# main.net
KiCad netlist of a schematic drawn in Altium Designer
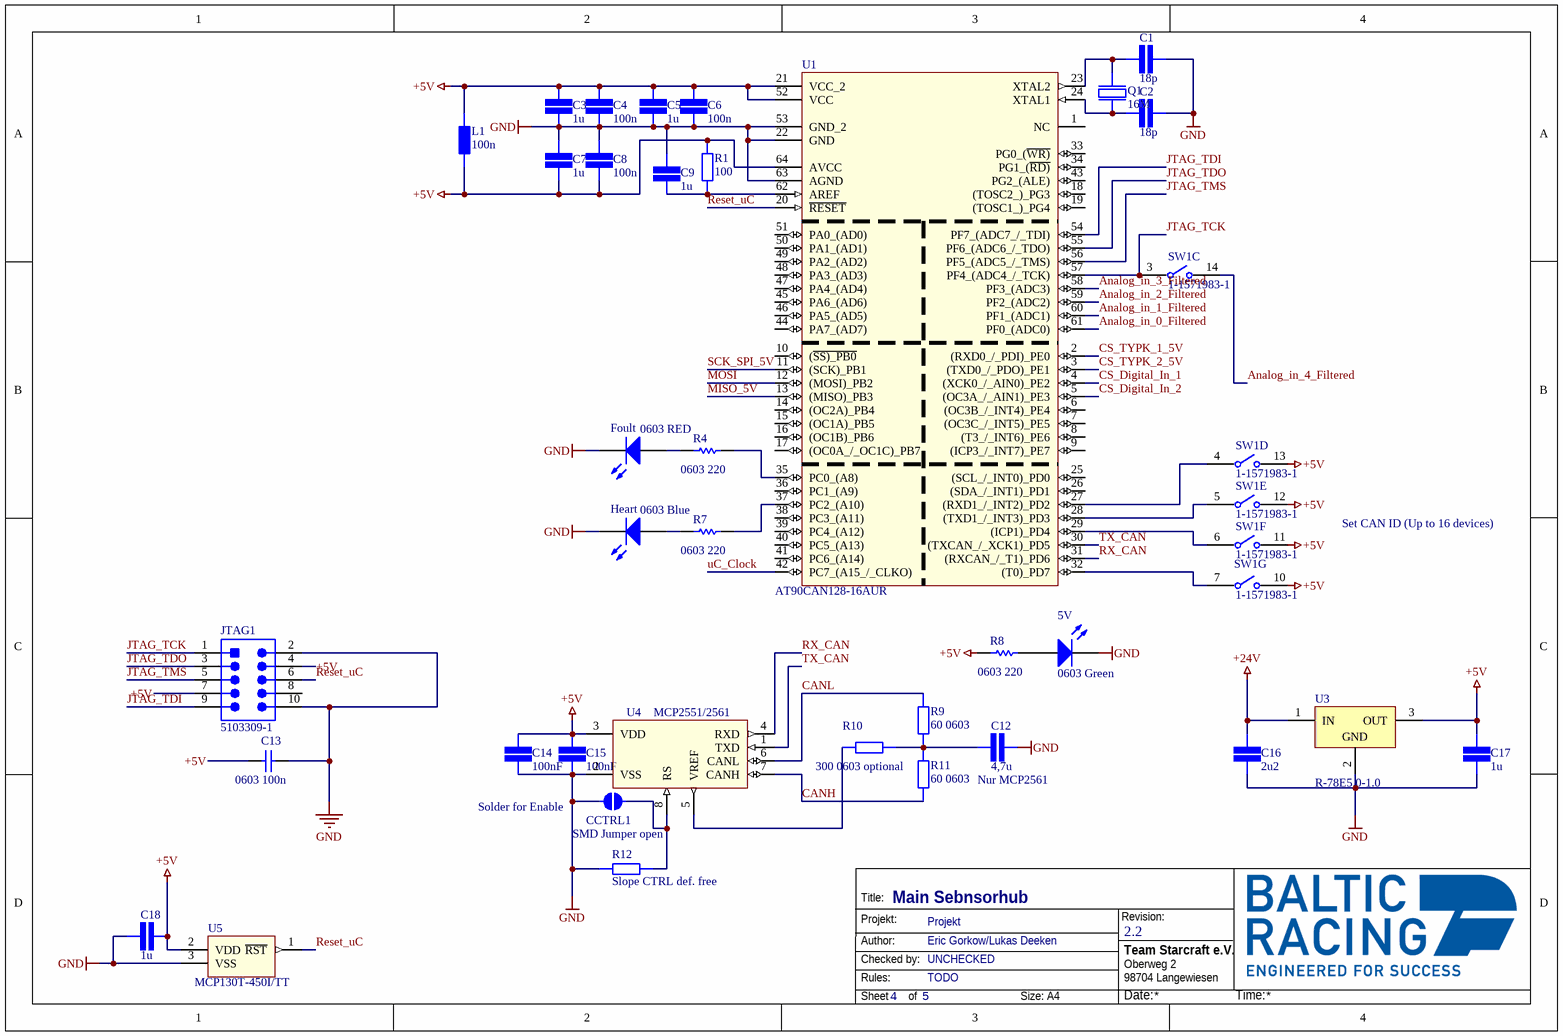
[diagram p0: main.SchDoc]

(export (version "E")
  (design (tool "Eeschema 10.0.6"))
  (components
    (comp (ref "5V")
      (value "0603 Green")
      (footprint "0603_A")
      (description "SMD mono-color Chip LED, WL-SMCW, Green")
      (fields (field (name "PARTNUMBER") "150060GS75000") (field (name "MANUFACTURER") "Wuerth Elektronik"))
      (libsource (lib "Altium Content Vault") (part "WE-LED_K1A2-2"))
    )
    (comp (ref "C1")
      (value "18p")
      (footprint "CAP 0603/1608")
      (description "Capacitor with multiple Footprints")
      (fields (field (name "Comment") "SMD Capacitor"))
      (libsource (lib "Standardbauteile") (part "SMD Capacitor"))
    )
    (comp (ref "C2")
      (value "18p")
      (footprint "CAP 0603/1608")
      (description "Capacitor with multiple Footprints")
      (fields (field (name "Comment") "SMD Capacitor"))
      (libsource (lib "Standardbauteile") (part "SMD Capacitor"))
    )
    (comp (ref "C3")
      (value "1u")
      (footprint "CAP 0603/1608")
      (description "Capacitor with multiple Footprints")
      (fields (field (name "Comment") "SMD Capacitor"))
      (libsource (lib "") (part "SMD Capacitor_1"))
    )
    (comp (ref "C4")
      (value "100n")
      (footprint "CAP 0603/1608")
      (description "Capacitor with multiple Footprints")
      (fields (field (name "Comment") "SMD Capacitor"))
      (libsource (lib "") (part "SMD Capacitor_1"))
    )
    (comp (ref "C5")
      (value "1u")
      (footprint "CAP 0603/1608")
      (description "Capacitor with multiple Footprints")
      (fields (field (name "Comment") "SMD Capacitor"))
      (libsource (lib "") (part "SMD Capacitor_1"))
    )
    (comp (ref "C6")
      (value "100n")
      (footprint "CAP 0603/1608")
      (description "Capacitor with multiple Footprints")
      (fields (field (name "Comment") "SMD Capacitor"))
      (libsource (lib "") (part "SMD Capacitor_1"))
    )
    (comp (ref "C7")
      (value "1u")
      (footprint "CAP 0603/1608")
      (description "Capacitor with multiple Footprints")
      (fields (field (name "Comment") "SMD Capacitor"))
      (libsource (lib "") (part "SMD Capacitor_1"))
    )
    (comp (ref "C8")
      (value "100n")
      (footprint "CAP 0603/1608")
      (description "Capacitor with multiple Footprints")
      (fields (field (name "Comment") "SMD Capacitor"))
      (libsource (lib "") (part "SMD Capacitor_1"))
    )
    (comp (ref "C9")
      (value "1u")
      (footprint "CAP 0603/1608")
      (description "Capacitor with multiple Footprints")
      (fields (field (name "Comment") "SMD Capacitor"))
      (libsource (lib "") (part "SMD Capacitor_1"))
    )
    (comp (ref "C12")
      (value "4,7u")
      (footprint "CAP 0603/1608")
      (description "Capacitor with multiple Footprints")
      (fields (field (name "Comment") "SMD Capacitor"))
      (libsource (lib "") (part "SMD Capacitor_2"))
    )
    (comp (ref "C13")
      (value "0603 100n")
      (footprint "CAPC0603(1608)100_L")
      (description "CAP 100nF 10V ±5% 0603 (1608 Metric) Thickness 1mm SMD")
      (fields (field (name "TOLERANCE") "Â±5%"))
      (libsource (lib "Altium Content Vault") (part "CAP"))
    )
    (comp (ref "C14")
      (value "100nF")
      (footprint "CAP 0603/1608")
      (description "Capacitor with multiple Footprints")
      (fields (field (name "Comment") "SMD Capacitor"))
      (libsource (lib "") (part "SMD Capacitor_1"))
    )
    (comp (ref "C15")
      (value "100nF")
      (footprint "CAP 0603/1608")
      (description "Capacitor with multiple Footprints")
      (fields (field (name "Comment") "SMD Capacitor"))
      (libsource (lib "") (part "SMD Capacitor_1"))
    )
    (comp (ref "C16")
      (value "2u2")
      (footprint "CAP 0603/1608")
      (description "Capacitor with multiple Footprints")
      (fields (field (name "Comment") "SMD Capacitor"))
      (libsource (lib "") (part "SMD Capacitor_1"))
    )
    (comp (ref "C17")
      (value "1u")
      (footprint "CAP 0603/1608")
      (description "Capacitor with multiple Footprints")
      (fields (field (name "Comment") "SMD Capacitor"))
      (libsource (lib "") (part "SMD Capacitor_1"))
    )
    (comp (ref "C18")
      (value "1u")
      (footprint "CAP 0603/1608")
      (description "Capacitor with multiple Footprints")
      (fields (field (name "Comment") "SMD Capacitor"))
      (libsource (lib "Standardbauteile") (part "SMD Capacitor"))
    )
    (comp (ref "CCTRL1")
      (value "SMD Jumper open")
      (footprint "SMD-JUMPER-OPEN")
      (libsource (lib "Standardbauteile") (part "SMD Jumper open"))
    )
    (comp (ref "Foult")
      (value "0603 RED")
      (footprint "0603_A")
      (description "SMD mono-color Chip LED, WL-SMCW, Blue")
      (fields (field (name "PARTNUMBER") "150060BS75000") (field (name "MANUFACTURER") "Wuerth Elektronik"))
      (libsource (lib "Altium Content Vault") (part "WE-LED_K1A2-2"))
    )
    (comp (ref "Heart")
      (value "0603 Blue")
      (footprint "0603_A")
      (description "SMD mono-color Chip LED, WL-SMCW, Blue")
      (fields (field (name "PARTNUMBER") "150060BS75000") (field (name "MANUFACTURER") "Wuerth Elektronik"))
      (libsource (lib "Altium Content Vault") (part "WE-LED_K1A2-2"))
    )
    (comp (ref "JTAG1")
      (value "5103309-1")
      (footprint "TECO-5103309-1_V")
      (fields (field (name "MANUFACTURER") "TE Connectivity"))
      (libsource (lib "Altium Content Vault") (part "CN-2P-M-R10"))
    )
    (comp (ref "L1")
      (value "100n")
      (footprint "SMD-Inductor 1206")
      (fields (field (name "Comment") "SMD Inductor"))
      (libsource (lib "Standardbauteile") (part "SMD Inductor"))
    )
    (comp (ref "Q1")
      (value "16M")
      (footprint "NDK NX5032GA")
      (description "16 MHz Quartz")
      (libsource (lib "Standardbauteile") (part "16 MHz Quartz"))
    )
    (comp (ref "R1")
      (value "100")
      (footprint "STACKPOLE CSR0603")
      (description "Resistor with multiple footprints")
      (fields (field (name "Comment") "SMD Resistor"))
      (libsource (lib "Standardbauteile") (part "SMD Resistor"))
    )
    (comp (ref "R4")
      (value "0603 220")
      (footprint "RESC1609X50X30NL10T20")
      (fields (field (name "MANUFACTURER") "Vishay Dale") (field (name "PART NUMBER") "CRCW0603130KFKEA"))
      (libsource (lib "Altium Content Vault") (part "RES"))
    )
    (comp (ref "R7")
      (value "0603 220")
      (footprint "RESC1609X50X30NL10T20")
      (fields (field (name "MANUFACTURER") "Vishay Dale") (field (name "PART NUMBER") "CRCW0603130KFKEA"))
      (libsource (lib "Altium Content Vault") (part "RES"))
    )
    (comp (ref "R8")
      (value "0603 220")
      (footprint "RESC1608X55X25ML10T15")
      (description "Chip Resistor, 100 Ohm, +/- 1%, 0.1 W, -55 to 155 degC, 0603 (1608 Metric), RoHS, Tape and Reel")
      (fields (field (name "TOLERANCE") "1%") (field (name "MANUFACTURER") "Yageo"))
      (libsource (lib "Altium Content Vault") (part "RES-2"))
    )
    (comp (ref "R9")
      (value "60 0603")
      (footprint "STACKPOLE CSR0603")
      (description "Resistor with multiple footprints")
      (fields (field (name "Comment") "SMD Resistor"))
      (libsource (lib "Standardbauteile") (part "SMD Resistor"))
    )
    (comp (ref "R10")
      (value "300 0603 optional")
      (footprint "STACKPOLE CSR0603")
      (description "Resistor with multiple footprints")
      (fields (field (name "Comment") "SMD Resistor"))
      (libsource (lib "Standardbauteile") (part "SMD Resistor"))
    )
    (comp (ref "R11")
      (value "60 0603")
      (footprint "STACKPOLE CSR0603")
      (description "Resistor with multiple footprints")
      (fields (field (name "Comment") "SMD Resistor"))
      (libsource (lib "Standardbauteile") (part "SMD Resistor"))
    )
    (comp (ref "R12")
      (value "Slope CTRL def. free")
      (footprint "STACKPOLE CSR0603")
      (description "Resistor with multiple footprints")
      (fields (field (name "Comment") "SMD Resistor"))
      (libsource (lib "Standardbauteile") (part "SMD Resistor"))
    )
    (comp (ref "SW1")
      (value "1-1571983-1")
      (footprint "FP-1-1571983-1-MFG")
      (description "SWITCH SLIDE DIP SPST 25MA 24V")
      (fields
        (field (name "MANUFACTURER") "TE Connectivity")
        (field (name "OCTOPART") "https://octopart.com/1-1571983-1-te+connectivity-40115518")
      )
      (libsource (lib "Altium Content Vault") (part "970e54b12a704161c1b4a03f85903bf"))
    )
    (comp (ref "U1")
      (value "AT90CAN128-16AUR")
      (footprint "*QFP80P1600X1600X120-64N")
      (description "Ic Mcu 8bit 128kb Flash 64tqfp")
      (fields (field (name "MP") "AT90CAN128-16AI") (field (name "MF") "Microchip"))
      (libsource (lib "Eric") (part "AT90CAN128-16AI"))
    )
    (comp (ref "U3")
      (value "R-78E5.0-1.0")
      (footprint "SIP3_RECOM")
      (description "Nonisolated 5V Switchmode converter")
      (libsource (lib "Standardbauteile") (part "R-78E05-1.0"))
    )
    (comp (ref "U4")
      (value "MCP2551/2561")
      (footprint "*SOIC127P600X175-8N")
      (description "MCP2551 Series 5.5 V 1 Mb/s Surface Mount High-Speed CAN Transceiver - SOIC-8")
      (fields (field (name "MP") "MCP2551-I/SN") (field (name "MF") "Microchip"))
      (libsource (lib "Eric") (part "MCP2551-I/SN"))
    )
    (comp (ref "U5")
      (value "MCP130T-450I/TT")
      (footprint "*SOT95P237X112-3N")
      (description "System Supervisors - Power Supply Monitors with Reset Generators Open Drain Low")
      (fields (field (name "MF") "Microchip") (field (name "MP") "MCP120T-450I/TT"))
      (libsource (lib "Eric") (part "MCP130T-450I/TT"))
    )
  )
  (nets
    (net (code "1") (name "+5V") (class "Default")
      (node (ref "C13") (pin "1") (pinfunction "1_1") (pintype "passive"))
      (node (ref "C14") (pin "2") (pinfunction "2_2") (pintype "passive"))
      (node (ref "C15") (pin "2") (pinfunction "2_2") (pintype "passive"))
      (node (ref "C17") (pin "2") (pinfunction "2_2") (pintype "passive"))
      (node (ref "C18") (pin "1") (pinfunction "1_1") (pintype "passive"))
      (node (ref "C3") (pin "2") (pinfunction "2_2") (pintype "passive"))
      (node (ref "C4") (pin "2") (pinfunction "2_2") (pintype "passive"))
      (node (ref "C5") (pin "2") (pinfunction "2_2") (pintype "passive"))
      (node (ref "C6") (pin "2") (pinfunction "2_2") (pintype "passive"))
      (node (ref "C7") (pin "1") (pinfunction "1_1") (pintype "passive"))
      (node (ref "C8") (pin "1") (pinfunction "1_1") (pintype "passive"))
      (node (ref "JTAG1") (pin "4") (pinfunction "4_4") (pintype "passive"))
      (node (ref "JTAG1") (pin "7") (pinfunction "7_7") (pintype "passive"))
      (node (ref "L1") (pin "1") (pinfunction "1_1") (pintype "passive"))
      (node (ref "L1") (pin "2") (pinfunction "2_2") (pintype "passive"))
      (node (ref "R1") (pin "2") (pinfunction "2_2") (pintype "passive"))
      (node (ref "R8") (pin "1") (pinfunction "1_1") (pintype "passive"))
      (node (ref "SW1") (pin "10") (pinfunction "10_10") (pintype "passive"))
      (node (ref "SW1") (pin "11") (pinfunction "11_11") (pintype "passive"))
      (node (ref "SW1") (pin "12") (pinfunction "12_12") (pintype "passive"))
      (node (ref "SW1") (pin "13") (pinfunction "13_13") (pintype "passive"))
      (node (ref "U1") (pin "21") (pinfunction "VCC_2_21") (pintype "power_in"))
      (node (ref "U1") (pin "52") (pinfunction "VCC_52") (pintype "power_in"))
      (node (ref "U1") (pin "64") (pinfunction "AVCC_64") (pintype "power_in"))
      (node (ref "U3") (pin "3") (pinfunction "OUT_3") (pintype "power_in"))
      (node (ref "U4") (pin "3") (pinfunction "VDD_3") (pintype "power_in"))
      (node (ref "U5") (pin "2") (pinfunction "VDD_2") (pintype "power_in"))
    )
    (net (code "2") (name "+24V") (class "Default")
      (node (ref "C16") (pin "2") (pinfunction "2_2") (pintype "passive"))
      (node (ref "U3") (pin "1") (pinfunction "IN_1") (pintype "power_in"))
    )
    (net (code "3") (name "/Analog_in_0_Filtered") (class "Default")
      (node (ref "U1") (pin "61") (pinfunction "PF0_(ADC0)_61") (pintype "bidirectional"))
    )
    (net (code "4") (name "/Analog_in_1_Filtered") (class "Default")
      (node (ref "U1") (pin "60") (pinfunction "PF1_(ADC1)_60") (pintype "bidirectional"))
    )
    (net (code "5") (name "/Analog_in_2_Filtered") (class "Default")
      (node (ref "U1") (pin "59") (pinfunction "PF2_(ADC2)_59") (pintype "bidirectional"))
    )
    (net (code "6") (name "/Analog_in_3_Filtered") (class "Default")
      (node (ref "U1") (pin "58") (pinfunction "PF3_(ADC3)_58") (pintype "bidirectional"))
    )
    (net (code "7") (name "/Analog_in_4_Filtered") (class "Default")
      (node (ref "SW1") (pin "14") (pinfunction "14_14") (pintype "passive"))
    )
    (net (code "8") (name "/CANH") (class "Default")
      (node (ref "R11") (pin "2") (pinfunction "2_2") (pintype "passive"))
      (node (ref "U4") (pin "7") (pinfunction "CANH_7") (pintype "bidirectional"))
    )
    (net (code "9") (name "/CANL") (class "Default")
      (node (ref "R9") (pin "1") (pinfunction "1_1") (pintype "passive"))
      (node (ref "U4") (pin "6") (pinfunction "CANL_6") (pintype "bidirectional"))
    )
    (net (code "10") (name "/CS_Digital_In_1") (class "Default")
      (node (ref "U1") (pin "4") (pinfunction "(XCK0_/_AIN0)_PE2_4") (pintype "bidirectional"))
    )
    (net (code "11") (name "/CS_Digital_In_2") (class "Default")
      (node (ref "U1") (pin "5") (pinfunction "(OC3A_/_AIN1)_PE3_5") (pintype "bidirectional"))
    )
    (net (code "12") (name "/CS_TYPK_1_5V") (class "Default")
      (node (ref "U1") (pin "2") (pinfunction "(RXD0_/_PDI)_PE0_2") (pintype "bidirectional"))
    )
    (net (code "13") (name "/CS_TYPK_2_5V") (class "Default")
      (node (ref "U1") (pin "3") (pinfunction "(TXD0_/_PDO)_PE1_3") (pintype "bidirectional"))
    )
    (net (code "14") (name "/JTAG_TCK") (class "Default")
      (node (ref "JTAG1") (pin "1") (pinfunction "1_1") (pintype "passive"))
      (node (ref "SW1") (pin "3") (pinfunction "3_3") (pintype "passive"))
      (node (ref "U1") (pin "57") (pinfunction "PF4_(ADC4_/_TCK)_57") (pintype "bidirectional"))
    )
    (net (code "15") (name "/JTAG_TDI") (class "Default")
      (node (ref "JTAG1") (pin "9") (pinfunction "9_9") (pintype "passive"))
      (node (ref "U1") (pin "54") (pinfunction "PF7_(ADC7_/_TDI)_54") (pintype "bidirectional"))
    )
    (net (code "16") (name "/JTAG_TDO") (class "Default")
      (node (ref "JTAG1") (pin "3") (pinfunction "3_3") (pintype "passive"))
      (node (ref "U1") (pin "55") (pinfunction "PF6_(ADC6_/_TDO)_55") (pintype "bidirectional"))
    )
    (net (code "17") (name "/JTAG_TMS") (class "Default")
      (node (ref "JTAG1") (pin "5") (pinfunction "5_5") (pintype "passive"))
      (node (ref "U1") (pin "56") (pinfunction "PF5_(ADC5_/_TMS)_56") (pintype "bidirectional"))
    )
    (net (code "18") (name "/MISO_5V") (class "Default")
      (node (ref "U1") (pin "13") (pinfunction "(MISO)_PB3_13") (pintype "bidirectional"))
    )
    (net (code "19") (name "/MOSI") (class "Default")
      (node (ref "U1") (pin "12") (pinfunction "(MOSI)_PB2_12") (pintype "bidirectional"))
    )
    (net (code "20") (name "/RX_CAN") (class "Default")
      (node (ref "U1") (pin "31") (pinfunction "(RXCAN_/_T1)_PD6_31") (pintype "bidirectional"))
      (node (ref "U4") (pin "4") (pinfunction "RXD_4") (pintype "output"))
    )
    (net (code "21") (name "/Reset_uC") (class "Default")
      (node (ref "JTAG1") (pin "6") (pinfunction "6_6") (pintype "passive"))
      (node (ref "U1") (pin "20") (pinfunction "~{RESET}_20") (pintype "input"))
      (node (ref "U5") (pin "1") (pinfunction "~{RST}_1") (pintype "output"))
    )
    (net (code "22") (name "/SCK_SPI_5V") (class "Default")
      (node (ref "U1") (pin "11") (pinfunction "(SCK)_PB1_11") (pintype "bidirectional"))
    )
    (net (code "23") (name "/TX_CAN") (class "Default")
      (node (ref "U1") (pin "30") (pinfunction "(TXCAN_/_XCK1)_PD5_30") (pintype "bidirectional"))
      (node (ref "U4") (pin "1") (pinfunction "TXD_1") (pintype "input"))
    )
    (net (code "24") (name "/uC_Clock") (class "Default")
      (node (ref "U1") (pin "42") (pinfunction "PC7_(A15_/_CLKO)_42") (pintype "bidirectional"))
    )
    (net (code "25") (name "GND") (class "Default")
      (node (ref "5V") (pin "1") (pinfunction "K_1") (pintype "passive"))
      (node (ref "C1") (pin "1") (pinfunction "1_1") (pintype "passive"))
      (node (ref "C12") (pin "2") (pinfunction "2_2") (pintype "passive"))
      (node (ref "C13") (pin "2") (pinfunction "2_2") (pintype "passive"))
      (node (ref "C14") (pin "1") (pinfunction "1_1") (pintype "passive"))
      (node (ref "C15") (pin "1") (pinfunction "1_1") (pintype "passive"))
      (node (ref "C16") (pin "1") (pinfunction "1_1") (pintype "passive"))
      (node (ref "C17") (pin "1") (pinfunction "1_1") (pintype "passive"))
      (node (ref "C18") (pin "2") (pinfunction "2_2") (pintype "passive"))
      (node (ref "C2") (pin "1") (pinfunction "1_1") (pintype "passive"))
      (node (ref "C3") (pin "1") (pinfunction "1_1") (pintype "passive"))
      (node (ref "C4") (pin "1") (pinfunction "1_1") (pintype "passive"))
      (node (ref "C5") (pin "1") (pinfunction "1_1") (pintype "passive"))
      (node (ref "C6") (pin "1") (pinfunction "1_1") (pintype "passive"))
      (node (ref "C7") (pin "2") (pinfunction "2_2") (pintype "passive"))
      (node (ref "C8") (pin "2") (pinfunction "2_2") (pintype "passive"))
      (node (ref "C9") (pin "2") (pinfunction "2_2") (pintype "passive"))
      (node (ref "CCTRL1") (pin "1") (pinfunction "1_1") (pintype "passive"))
      (node (ref "Foult") (pin "1") (pinfunction "K_1") (pintype "passive"))
      (node (ref "Heart") (pin "1") (pinfunction "K_1") (pintype "passive"))
      (node (ref "JTAG1") (pin "10") (pinfunction "10_10") (pintype "passive"))
      (node (ref "JTAG1") (pin "2") (pinfunction "2_2") (pintype "passive"))
      (node (ref "R12") (pin "1") (pinfunction "1_1") (pintype "passive"))
      (node (ref "U1") (pin "22") (pinfunction "GND_22") (pintype "passive"))
      (node (ref "U1") (pin "53") (pinfunction "GND_2_53") (pintype "passive"))
      (node (ref "U1") (pin "63") (pinfunction "AGND_63") (pintype "passive"))
      (node (ref "U3") (pin "2") (pinfunction "GND_2") (pintype "power_in"))
      (node (ref "U4") (pin "2") (pinfunction "VSS_2") (pintype "passive"))
      (node (ref "U5") (pin "3") (pinfunction "VSS_3") (pintype "power_in"))
    )
    (net (code "26") (name "Net-(5V-A)") (class "Default")
      (node (ref "5V") (pin "2") (pinfunction "A_2") (pintype "passive"))
      (node (ref "R8") (pin "2") (pinfunction "2_2") (pintype "passive"))
    )
    (net (code "27") (name "Net-(C12-Pad1)") (class "Default")
      (node (ref "C12") (pin "1") (pinfunction "1_1") (pintype "passive"))
      (node (ref "R10") (pin "2") (pinfunction "2_2") (pintype "passive"))
      (node (ref "R11") (pin "1") (pinfunction "1_1") (pintype "passive"))
      (node (ref "R9") (pin "2") (pinfunction "2_2") (pintype "passive"))
    )
    (net (code "28") (name "Net-(Foult-A)") (class "Default")
      (node (ref "Foult") (pin "2") (pinfunction "A_2") (pintype "passive"))
      (node (ref "R4") (pin "2") (pinfunction "2_2") (pintype "passive"))
    )
    (net (code "29") (name "Net-(Heart-A)") (class "Default")
      (node (ref "Heart") (pin "2") (pinfunction "A_2") (pintype "passive"))
      (node (ref "R7") (pin "2") (pinfunction "2_2") (pintype "passive"))
    )
    (net (code "30") (name "Net-(U1-(ICP1)_PD4)") (class "Default")
      (node (ref "SW1") (pin "6") (pinfunction "6_6") (pintype "passive"))
      (node (ref "U1") (pin "29") (pinfunction "(ICP1)_PD4_29") (pintype "bidirectional"))
    )
    (net (code "31") (name "Net-(U1-(RXD1_{slash}_INT2)_PD2)") (class "Default")
      (node (ref "SW1") (pin "4") (pinfunction "4_4") (pintype "passive"))
      (node (ref "U1") (pin "27") (pinfunction "(RXD1_/_INT2)_PD2_27") (pintype "bidirectional"))
    )
    (net (code "32") (name "Net-(U1-(T0)_PD7)") (class "Default")
      (node (ref "SW1") (pin "7") (pinfunction "7_7") (pintype "passive"))
      (node (ref "U1") (pin "32") (pinfunction "(T0)_PD7_32") (pintype "bidirectional"))
    )
    (net (code "33") (name "Net-(U1-(TXD1_{slash}_INT3)_PD3)") (class "Default")
      (node (ref "SW1") (pin "5") (pinfunction "5_5") (pintype "passive"))
      (node (ref "U1") (pin "28") (pinfunction "(TXD1_/_INT3)_PD3_28") (pintype "bidirectional"))
    )
    (net (code "34") (name "Net-(U1-AREF)") (class "Default")
      (node (ref "C9") (pin "1") (pinfunction "1_1") (pintype "passive"))
      (node (ref "R1") (pin "1") (pinfunction "1_1") (pintype "passive"))
      (node (ref "U1") (pin "62") (pinfunction "AREF_62") (pintype "input"))
    )
    (net (code "35") (name "Net-(U1-PC0_(A8))") (class "Default")
      (node (ref "R4") (pin "1") (pinfunction "1_1") (pintype "passive"))
      (node (ref "U1") (pin "35") (pinfunction "PC0_(A8)_35") (pintype "bidirectional"))
    )
    (net (code "36") (name "Net-(U1-PC2_(A10))") (class "Default")
      (node (ref "R7") (pin "1") (pinfunction "1_1") (pintype "passive"))
      (node (ref "U1") (pin "37") (pinfunction "PC2_(A10)_37") (pintype "bidirectional"))
    )
    (net (code "37") (name "Net-(U1-XTAL1)") (class "Default")
      (node (ref "C2") (pin "2") (pinfunction "2_2") (pintype "passive"))
      (node (ref "Q1") (pin "1") (pinfunction "1_1") (pintype "passive"))
      (node (ref "U1") (pin "24") (pinfunction "XTAL1_24") (pintype "input"))
    )
    (net (code "38") (name "Net-(U1-XTAL2)") (class "Default")
      (node (ref "C1") (pin "2") (pinfunction "2_2") (pintype "passive"))
      (node (ref "Q1") (pin "2") (pinfunction "2_2") (pintype "passive"))
      (node (ref "U1") (pin "23") (pinfunction "XTAL2_23") (pintype "output"))
    )
    (net (code "39") (name "Net-(U4-RS)") (class "Default")
      (node (ref "CCTRL1") (pin "2") (pinfunction "2_2") (pintype "passive"))
      (node (ref "R12") (pin "2") (pinfunction "2_2") (pintype "passive"))
      (node (ref "U4") (pin "8") (pinfunction "RS_8") (pintype "input"))
    )
    (net (code "40") (name "Net-(U4-VREF)") (class "Default")
      (node (ref "R10") (pin "1") (pinfunction "1_1") (pintype "passive"))
      (node (ref "U4") (pin "5") (pinfunction "VREF_5") (pintype "output"))
    )
    (net (code "41") (name "unconnected-(JTAG1-Pad8)") (class "Default")
      (node (ref "JTAG1") (pin "8") (pinfunction "8_8") (pintype "passive"))
    )
    (net (code "42") (name "unconnected-(U1-(ICP3_{slash}_INT7)_PE7-Pad9)") (class "Default")
      (node (ref "U1") (pin "9") (pinfunction "(ICP3_/_INT7)_PE7_9") (pintype "bidirectional"))
    )
    (net (code "43") (name "unconnected-(U1-(OC0A_{slash}_OC1C)_PB7-Pad17)") (class "Default")
      (node (ref "U1") (pin "17") (pinfunction "(OC0A_/_OC1C)_PB7_17") (pintype "bidirectional"))
    )
    (net (code "44") (name "unconnected-(U1-(OC1A)_PB5-Pad15)") (class "Default")
      (node (ref "U1") (pin "15") (pinfunction "(OC1A)_PB5_15") (pintype "bidirectional"))
    )
    (net (code "45") (name "unconnected-(U1-(OC1B)_PB6-Pad16)") (class "Default")
      (node (ref "U1") (pin "16") (pinfunction "(OC1B)_PB6_16") (pintype "bidirectional"))
    )
    (net (code "46") (name "unconnected-(U1-(OC2A)_PB4-Pad14)") (class "Default")
      (node (ref "U1") (pin "14") (pinfunction "(OC2A)_PB4_14") (pintype "bidirectional"))
    )
    (net (code "47") (name "unconnected-(U1-(OC3B_{slash}_INT4)_PE4-Pad6)") (class "Default")
      (node (ref "U1") (pin "6") (pinfunction "(OC3B_/_INT4)_PE4_6") (pintype "bidirectional"))
    )
    (net (code "48") (name "unconnected-(U1-(OC3C_{slash}_INT5)_PE5-Pad7)") (class "Default")
      (node (ref "U1") (pin "7") (pinfunction "(OC3C_/_INT5)_PE5_7") (pintype "bidirectional"))
    )
    (net (code "49") (name "unconnected-(U1-(SCL_{slash}_INT0)_PD0-Pad25)") (class "Default")
      (node (ref "U1") (pin "25") (pinfunction "(SCL_/_INT0)_PD0_25") (pintype "bidirectional"))
    )
    (net (code "50") (name "unconnected-(U1-(SDA_{slash}_INT1)_PD1-Pad26)") (class "Default")
      (node (ref "U1") (pin "26") (pinfunction "(SDA_/_INT1)_PD1_26") (pintype "bidirectional"))
    )
    (net (code "51") (name "unconnected-(U1-(T3_{slash}_INT6)_PE6-Pad8)") (class "Default")
      (node (ref "U1") (pin "8") (pinfunction "(T3_/_INT6)_PE6_8") (pintype "bidirectional"))
    )
    (net (code "52") (name "unconnected-(U1-(TOSC1_)_PG4-Pad19)") (class "Default")
      (node (ref "U1") (pin "19") (pinfunction "(TOSC1_)_PG4_19") (pintype "bidirectional"))
    )
    (net (code "53") (name "unconnected-(U1-(TOSC2_)_PG3-Pad18)") (class "Default")
      (node (ref "U1") (pin "18") (pinfunction "(TOSC2_)_PG3_18") (pintype "bidirectional"))
    )
    (net (code "54") (name "unconnected-(U1-(~{SS)_PB0}-Pad10)") (class "Default")
      (node (ref "U1") (pin "10") (pinfunction "(~{SS)_PB0}_10") (pintype "bidirectional"))
    )
    (net (code "55") (name "unconnected-(U1-NC-Pad1)") (class "Default")
      (node (ref "U1") (pin "1") (pinfunction "NC_1") (pintype "passive"))
    )
    (net (code "56") (name "unconnected-(U1-PA0_(AD0)-Pad51)") (class "Default")
      (node (ref "U1") (pin "51") (pinfunction "PA0_(AD0)_51") (pintype "bidirectional"))
    )
    (net (code "57") (name "unconnected-(U1-PA1_(AD1)-Pad50)") (class "Default")
      (node (ref "U1") (pin "50") (pinfunction "PA1_(AD1)_50") (pintype "bidirectional"))
    )
    (net (code "58") (name "unconnected-(U1-PA2_(AD2)-Pad49)") (class "Default")
      (node (ref "U1") (pin "49") (pinfunction "PA2_(AD2)_49") (pintype "bidirectional"))
    )
    (net (code "59") (name "unconnected-(U1-PA3_(AD3)-Pad48)") (class "Default")
      (node (ref "U1") (pin "48") (pinfunction "PA3_(AD3)_48") (pintype "bidirectional"))
    )
    (net (code "60") (name "unconnected-(U1-PA4_(AD4)-Pad47)") (class "Default")
      (node (ref "U1") (pin "47") (pinfunction "PA4_(AD4)_47") (pintype "bidirectional"))
    )
    (net (code "61") (name "unconnected-(U1-PA5_(AD5)-Pad46)") (class "Default")
      (node (ref "U1") (pin "46") (pinfunction "PA5_(AD5)_46") (pintype "bidirectional"))
    )
    (net (code "62") (name "unconnected-(U1-PA6_(AD6)-Pad45)") (class "Default")
      (node (ref "U1") (pin "45") (pinfunction "PA6_(AD6)_45") (pintype "bidirectional"))
    )
    (net (code "63") (name "unconnected-(U1-PA7_(AD7)-Pad44)") (class "Default")
      (node (ref "U1") (pin "44") (pinfunction "PA7_(AD7)_44") (pintype "bidirectional"))
    )
    (net (code "64") (name "unconnected-(U1-PC1_(A9)-Pad36)") (class "Default")
      (node (ref "U1") (pin "36") (pinfunction "PC1_(A9)_36") (pintype "bidirectional"))
    )
    (net (code "65") (name "unconnected-(U1-PC3_(A11)-Pad38)") (class "Default")
      (node (ref "U1") (pin "38") (pinfunction "PC3_(A11)_38") (pintype "bidirectional"))
    )
    (net (code "66") (name "unconnected-(U1-PC4_(A12)-Pad39)") (class "Default")
      (node (ref "U1") (pin "39") (pinfunction "PC4_(A12)_39") (pintype "bidirectional"))
    )
    (net (code "67") (name "unconnected-(U1-PC5_(A13)-Pad40)") (class "Default")
      (node (ref "U1") (pin "40") (pinfunction "PC5_(A13)_40") (pintype "bidirectional"))
    )
    (net (code "68") (name "unconnected-(U1-PC6_(A14)-Pad41)") (class "Default")
      (node (ref "U1") (pin "41") (pinfunction "PC6_(A14)_41") (pintype "bidirectional"))
    )
    (net (code "69") (name "unconnected-(U1-PG0_(~{WR)}-Pad33)") (class "Default")
      (node (ref "U1") (pin "33") (pinfunction "PG0_(~{WR)}_33") (pintype "bidirectional"))
    )
    (net (code "70") (name "unconnected-(U1-PG1_(~{RD)}-Pad34)") (class "Default")
      (node (ref "U1") (pin "34") (pinfunction "PG1_(~{RD)}_34") (pintype "bidirectional"))
    )
    (net (code "71") (name "unconnected-(U1-PG2_(ALE)-Pad43)") (class "Default")
      (node (ref "U1") (pin "43") (pinfunction "PG2_(ALE)_43") (pintype "bidirectional"))
    )
  )
)
